# PowerSupply.net
KiCad netlist of a schematic drawn in EAGLE
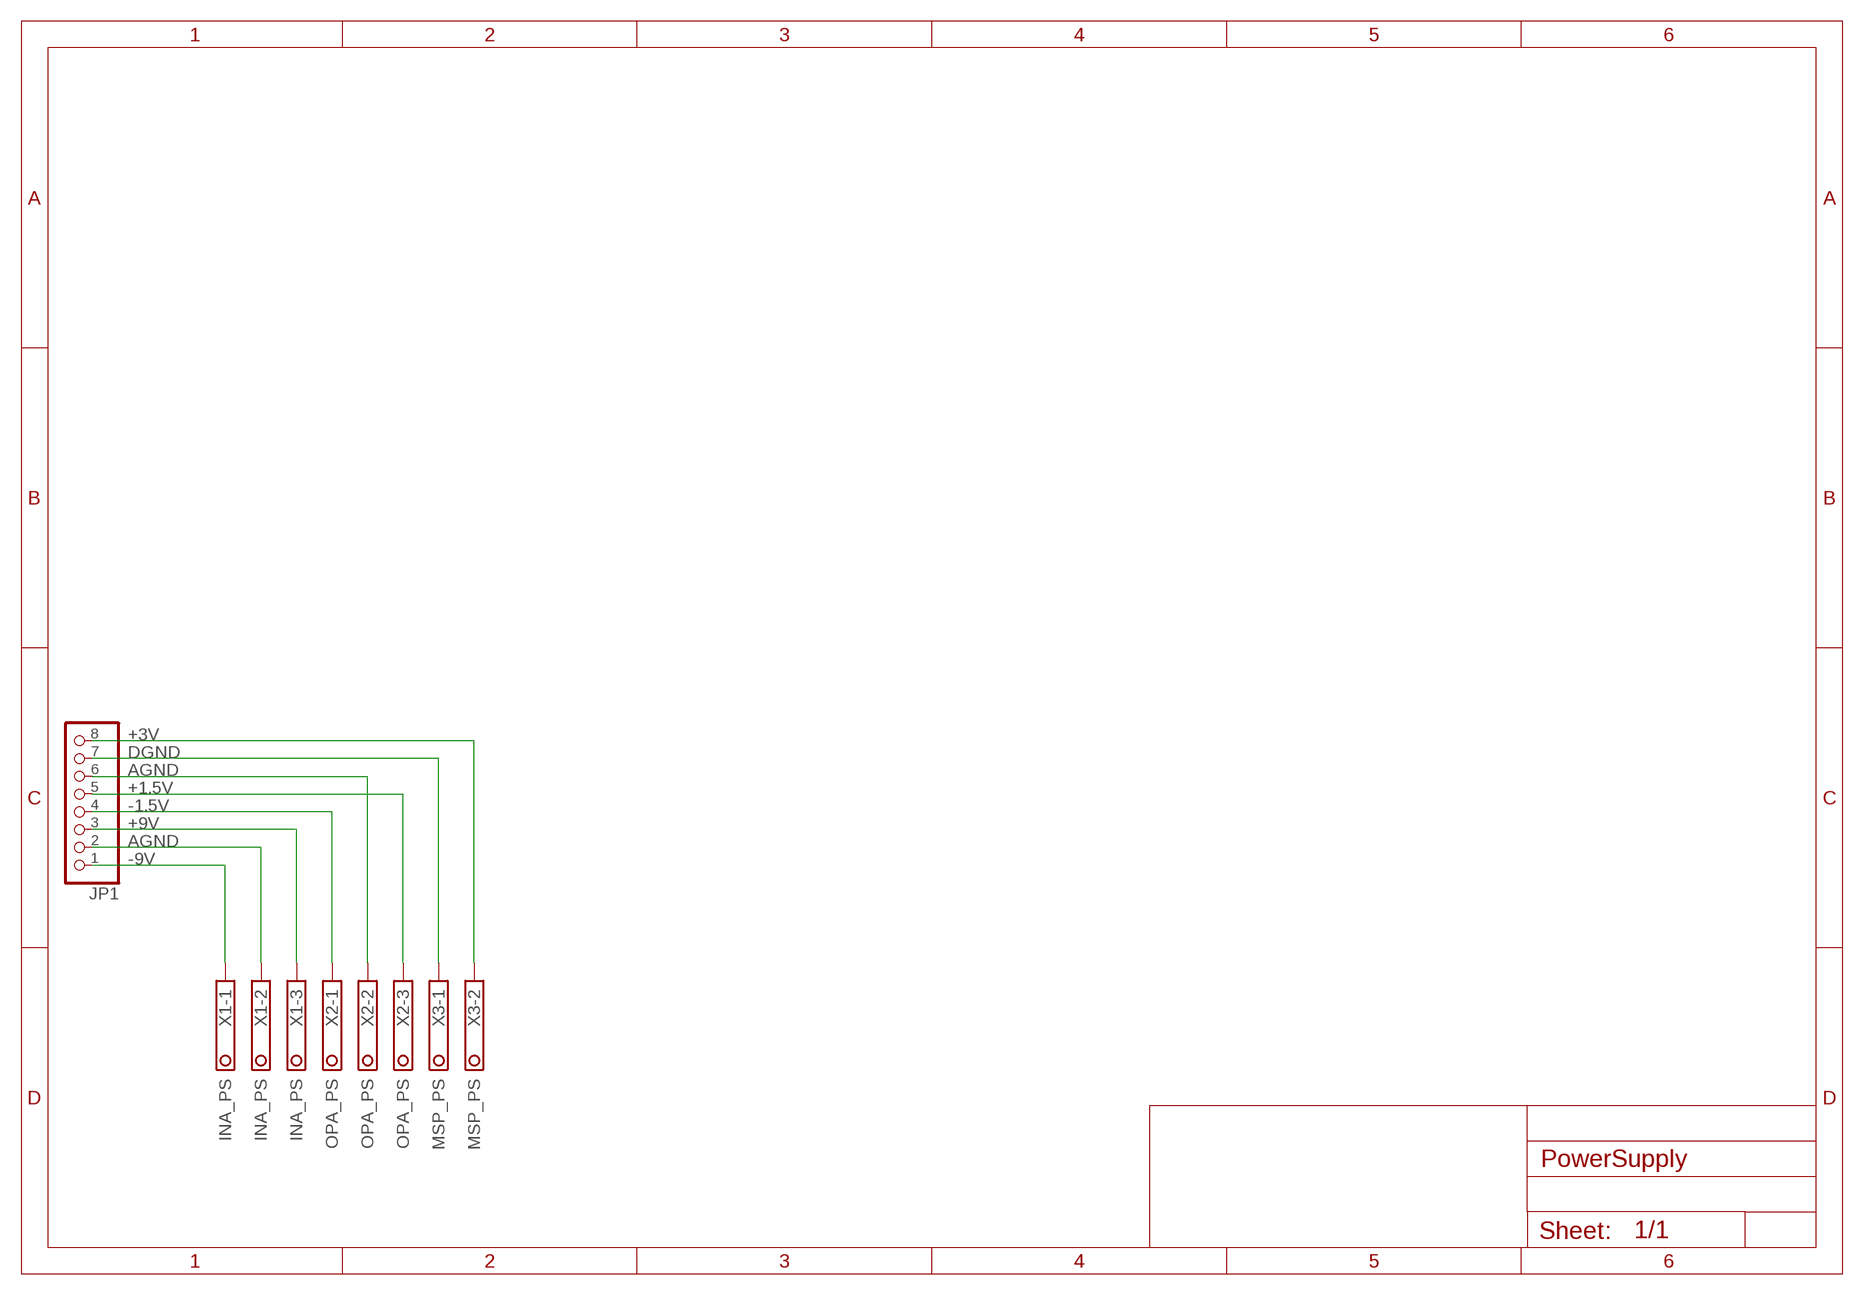
[diagram p0: schematic, sheet 1]

(export (version "E")
  (design (tool "Eeschema 10.0.6"))
  (components
    (comp (ref "JP1")
      (value "PINHD-1X8")
      (footprint "eagle-import:1X08")
      (libsource (lib "eagle-import") (part "PINHD-1X8"))
    )
    (comp (ref "X1")
      (value "INA_PS")
      (footprint "eagle-import:1751251")
      (fields (field (name "MF") "Phoenix Contact") (field (name "MP") "1751251"))
      (libsource (lib "eagle-import") (part "1751251"))
    )
    (comp (ref "X2")
      (value "OPA_PS")
      (footprint "eagle-import:1751251")
      (fields (field (name "MF") "Phoenix Contact") (field (name "MP") "1751251"))
      (libsource (lib "eagle-import") (part "1751251"))
    )
    (comp (ref "X3")
      (value "MSP_PS")
      (footprint "eagle-import:1751248")
      (fields (field (name "MF") "Phoenix Contact") (field (name "MP") "1751248"))
      (libsource (lib "eagle-import") (part "1751248"))
    )
  )
  (nets
    (net (code "1") (name "/+1.5V") (class "Default")
      (node (ref "JP1") (pin "5") (pinfunction "5_5") (pintype "passive"))
      (node (ref "X2") (pin "3") (pinfunction "K_3") (pintype "passive"))
    )
    (net (code "2") (name "/+3V") (class "Default")
      (node (ref "JP1") (pin "8") (pinfunction "8_8") (pintype "passive"))
      (node (ref "X3") (pin "2") (pinfunction "K_2") (pintype "passive"))
    )
    (net (code "3") (name "/+9V") (class "Default")
      (node (ref "JP1") (pin "3") (pinfunction "3_3") (pintype "passive"))
      (node (ref "X1") (pin "3") (pinfunction "K_3") (pintype "passive"))
    )
    (net (code "4") (name "/-1.5V") (class "Default")
      (node (ref "JP1") (pin "4") (pinfunction "4_4") (pintype "passive"))
      (node (ref "X2") (pin "1") (pinfunction "K_1") (pintype "passive"))
    )
    (net (code "5") (name "/-9V") (class "Default")
      (node (ref "JP1") (pin "1") (pinfunction "1_1") (pintype "passive"))
      (node (ref "X1") (pin "1") (pinfunction "K_1") (pintype "passive"))
    )
    (net (code "6") (name "/AGND") (class "Default")
      (node (ref "JP1") (pin "2") (pinfunction "2_2") (pintype "passive"))
      (node (ref "JP1") (pin "6") (pinfunction "6_6") (pintype "passive"))
      (node (ref "X1") (pin "2") (pinfunction "K_2") (pintype "passive"))
      (node (ref "X2") (pin "2") (pinfunction "K_2") (pintype "passive"))
    )
    (net (code "7") (name "/DGND") (class "Default")
      (node (ref "JP1") (pin "7") (pinfunction "7_7") (pintype "passive"))
      (node (ref "X3") (pin "1") (pinfunction "K_1") (pintype "passive"))
    )
  )
)
